# PIC.net
KiCad netlist of a schematic drawn in Altium Designer
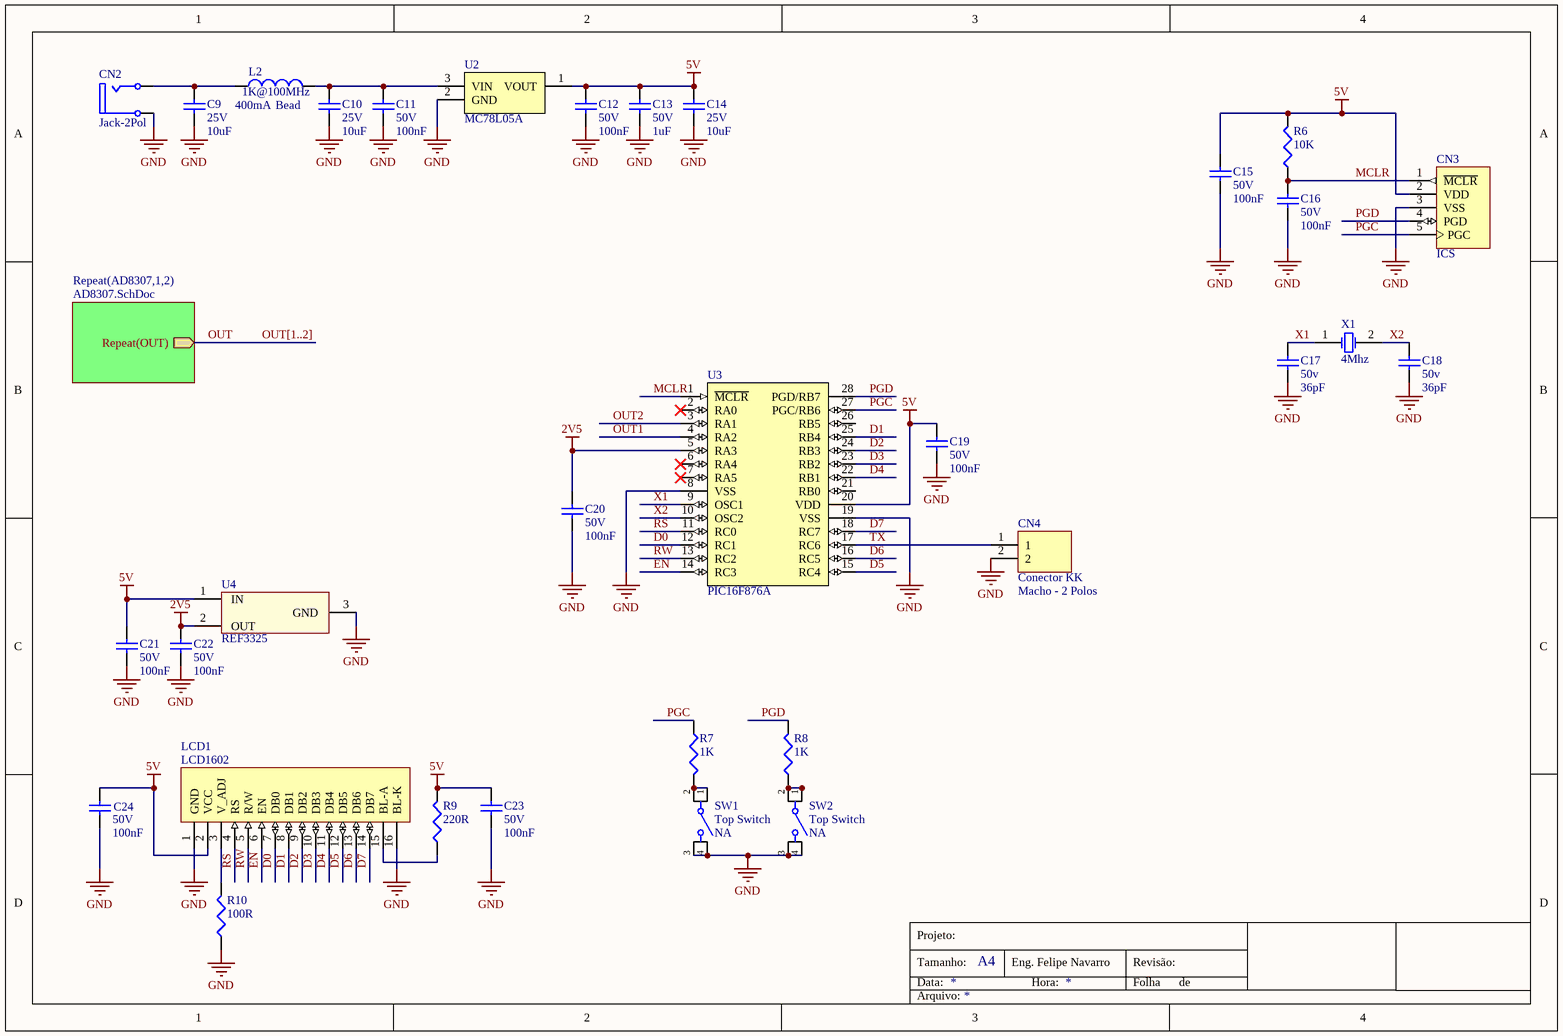
[diagram p0: PIC.SchDoc]

(export (version "E")
  (design (tool "Eeschema 10.0.6"))
  (components
    (comp (ref "C9")
      (value "10uF")
      (footprint "CC0805")
      (description "Capacitor (Semiconductor SIM Model)")
      (fields (field (name "TENSÃO") "25V") (field (name "Comment") "Capacitor Cerâmico"))
      (libsource (lib "NavarroCAP") (part "Cap 10uF 25V 0805 X5R"))
    )
    (comp (ref "C10")
      (value "10uF")
      (footprint "CC0805")
      (description "Capacitor (Semiconductor SIM Model)")
      (fields (field (name "TENSÃO") "25V") (field (name "Comment") "Capacitor Cerâmico"))
      (libsource (lib "NavarroCAP") (part "Cap 10uF 25V 0805 X5R"))
    )
    (comp (ref "C11")
      (value "100nF")
      (footprint "CC0603")
      (description "Capacitor (Semiconductor SIM Model)")
      (fields (field (name "TENSÃO") "50V") (field (name "Comment") "Capacitor Cerâmico"))
      (libsource (lib "NavarroCAP") (part "Cap 100nF 50V 0603 X7R"))
    )
    (comp (ref "C12")
      (value "100nF")
      (footprint "CC0603")
      (description "Capacitor (Semiconductor SIM Model)")
      (fields (field (name "TENSÃO") "50V") (field (name "Comment") "Capacitor Cerâmico"))
      (libsource (lib "NavarroCAP") (part "Cap 100nF 50V 0603 X7R"))
    )
    (comp (ref "C13")
      (value "1uF")
      (footprint "CC0603")
      (description "Capacitor (Semiconductor SIM Model)")
      (fields (field (name "TENSÃO") "50V") (field (name "Comment") "Capacitor Cerâmico"))
      (libsource (lib "NavarroCAP") (part "Cap 1uF 50V 0603 X5R"))
    )
    (comp (ref "C14")
      (value "10uF")
      (footprint "CC0805")
      (description "Capacitor (Semiconductor SIM Model)")
      (fields (field (name "TENSÃO") "25V") (field (name "Comment") "Capacitor Cerâmico"))
      (libsource (lib "NavarroCAP") (part "Cap 10uF 25V 0805 X5R"))
    )
    (comp (ref "C15")
      (value "100nF")
      (footprint "CC0603")
      (description "Capacitor (Semiconductor SIM Model)")
      (fields (field (name "TENSÃO") "50V") (field (name "Comment") "Capacitor Cerâmico"))
      (libsource (lib "NavarroCAP") (part "Cap 100nF 50V 0603 X7R"))
    )
    (comp (ref "C16")
      (value "100nF")
      (footprint "CC0603")
      (description "Capacitor (Semiconductor SIM Model)")
      (fields (field (name "TENSÃO") "50V") (field (name "Comment") "Capacitor Cerâmico"))
      (libsource (lib "NavarroCAP") (part "Cap 100nF 50V 0603 X7R"))
    )
    (comp (ref "C17")
      (value "36pF")
      (footprint "CC0603")
      (description "Capacitor (Semiconductor SIM Model)")
      (fields (field (name "TENSÃO") "50v") (field (name "Comment") "Capacitor Cerâmico"))
      (libsource (lib "NavarroCAP") (part "Cap - $Val $V $Footprint $Classe_1"))
    )
    (comp (ref "C18")
      (value "36pF")
      (footprint "CC0603")
      (description "Capacitor (Semiconductor SIM Model)")
      (fields (field (name "TENSÃO") "50v") (field (name "Comment") "Capacitor Cerâmico"))
      (libsource (lib "NavarroCAP") (part "Cap - $Val $V $Footprint $Classe_1"))
    )
    (comp (ref "C19")
      (value "100nF")
      (footprint "CC0603")
      (description "Capacitor (Semiconductor SIM Model)")
      (fields (field (name "TENSÃO") "50V") (field (name "Comment") "Capacitor Cerâmico"))
      (libsource (lib "NavarroCAP") (part "Cap 100nF 50V 0603 X7R"))
    )
    (comp (ref "C20")
      (value "100nF")
      (footprint "CC0603")
      (description "Capacitor (Semiconductor SIM Model)")
      (fields (field (name "TENSÃO") "50V") (field (name "Comment") "Capacitor Cerâmico"))
      (libsource (lib "NavarroCAP") (part "Cap 100nF 50V 0603 X7R"))
    )
    (comp (ref "C21")
      (value "100nF")
      (footprint "CC0603")
      (description "Capacitor (Semiconductor SIM Model)")
      (fields (field (name "TENSÃO") "50V") (field (name "Comment") "Capacitor Cerâmico"))
      (libsource (lib "NavarroCAP") (part "Cap 100nF 50V 0603 X7R"))
    )
    (comp (ref "C22")
      (value "100nF")
      (footprint "CC0603")
      (description "Capacitor (Semiconductor SIM Model)")
      (fields (field (name "TENSÃO") "50V") (field (name "Comment") "Capacitor Cerâmico"))
      (libsource (lib "NavarroCAP") (part "Cap 100nF 50V 0603 X7R"))
    )
    (comp (ref "C23")
      (value "100nF")
      (footprint "CC0603")
      (description "Capacitor (Semiconductor SIM Model)")
      (fields (field (name "TENSÃO") "50V") (field (name "Comment") "Capacitor Cerâmico"))
      (libsource (lib "NavarroCAP") (part "Cap 100nF 50V 0603 X7R"))
    )
    (comp (ref "C24")
      (value "100nF")
      (footprint "CC0603")
      (description "Capacitor (Semiconductor SIM Model)")
      (fields (field (name "TENSÃO") "50V") (field (name "Comment") "Capacitor Cerâmico"))
      (libsource (lib "NavarroCAP") (part "Cap 100nF 50V 0603 X7R"))
    )
    (comp (ref "CN2")
      (value "Jack-2Pol")
      (footprint "CONN_JACK-FONTE")
      (description "Jack Socket, Thru-Hole, Vertical, 2-Conductor Open Circuit")
      (libsource (lib "NavarroCON") (part "Jack-2Pol"))
    )
    (comp (ref "CN3")
      (value "ICS")
      (footprint "CONN HDR1X5")
      (description "Header, 5-Pin")
      (libsource (lib "NavarroCON") (part "Header 5 ICS"))
    )
    (comp (ref "CN4")
      (value "Conector KK")
      (footprint "CONN HDR2-POL P.100")
      (fields (field (name "ALTIUM_VALUE") "Macho - 2 Polos"))
      (libsource (lib "NavarroCON") (part "KK 2P Macho-V P2.54mm"))
    )
    (comp (ref "L2")
      (value "Bead")
      (footprint "CC0603")
      (fields (field (name "CORRENTE") "400mA") (field (name "ALTIUM_VALUE") "1K@100MHz"))
      (libsource (lib "NavarroIND") (part "Bd 1K@100MHz 0603 400mA"))
    )
    (comp (ref "LCD1")
      (value "LCD1602")
      (footprint "LCD-1602")
      (description "LCD Generico 16 caracteres X 2 linhas")
      (libsource (lib "Navarro") (part "LCD1602"))
    )
    (comp (ref "R6")
      (value "10K")
      (footprint "CC0603")
      (description "Resistor")
      (libsource (lib "NavarroRES") (part "Res 10K 1% 0603 1/10W"))
    )
    (comp (ref "R7")
      (value "1K")
      (footprint "CC0603")
      (description "Resistor")
      (libsource (lib "NavarroRES") (part "Res 1K 1% 0603 1/10W"))
    )
    (comp (ref "R8")
      (value "1K")
      (footprint "CC0603")
      (description "Resistor")
      (libsource (lib "NavarroRES") (part "Res 1K 1% 0603 1/10W"))
    )
    (comp (ref "R9")
      (value "220R")
      (footprint "CC0603")
      (description "Resistor")
      (libsource (lib "NavarroRES") (part "Res 220R 1% 0603 1/10W"))
    )
    (comp (ref "R10")
      (value "100R")
      (footprint "CC0603")
      (description "Resistor")
      (libsource (lib "NavarroRES") (part "Res 220R 1% 0603 1/10W"))
    )
    (comp (ref "SW1")
      (value "Top Switch")
      (footprint "SWITCH-TACTIL_6x6")
      (description "Single-Pole, Single-Throw Switch")
      (fields (field (name "ALTIUM_VALUE") "NA"))
      (libsource (lib "Tecnoclade") (part "SW-SPST Tactil"))
    )
    (comp (ref "SW2")
      (value "Top Switch")
      (footprint "SWITCH-TACTIL_6x6")
      (description "Single-Pole, Single-Throw Switch")
      (fields (field (name "ALTIUM_VALUE") "NA"))
      (libsource (lib "Tecnoclade") (part "SW-SPST Tactil"))
    )
    (comp (ref "U2")
      (value "MC78L05A")
      (footprint "SOT-89-3N")
      (description "Regulador Linear 5V")
      (libsource (lib "Navarro") (part "MC78L05"))
    )
    (comp (ref "U3")
      (value "PIC16F876A")
      (footprint "SOIC-28N")
      (description "Microcontrolador PIC")
      (libsource (lib "Navarro") (part "PIC16F876A"))
    )
    (comp (ref "U4")
      (value "REF3325")
      (footprint "SOT-23-3N")
      (description "IC VREF SERIES 2.5V")
      (libsource (lib "Navarro") (part "REF3325"))
    )
    (comp (ref "X1")
      (value "4Mhz")
      (footprint "HC/49US")
      (description "Crystal Oscillator")
      (libsource (lib "Navarro") (part "XTAL"))
    )
  )
  (nets
    (net (code "1") (name "/D0") (class "Default")
      (node (ref "LCD1") (pin "7") (pinfunction "DB0_7") (pintype "bidirectional"))
      (node (ref "U3") (pin "12") (pinfunction "RC1_12") (pintype "bidirectional"))
    )
    (net (code "2") (name "/D1") (class "Default")
      (node (ref "LCD1") (pin "8") (pinfunction "DB1_8") (pintype "bidirectional"))
      (node (ref "U3") (pin "25") (pinfunction "RB4_25") (pintype "bidirectional"))
    )
    (net (code "3") (name "/D2") (class "Default")
      (node (ref "LCD1") (pin "9") (pinfunction "DB2_9") (pintype "bidirectional"))
      (node (ref "U3") (pin "24") (pinfunction "RB3_24") (pintype "bidirectional"))
    )
    (net (code "4") (name "/D3") (class "Default")
      (node (ref "LCD1") (pin "10") (pinfunction "DB3_10") (pintype "bidirectional"))
      (node (ref "U3") (pin "23") (pinfunction "RB2_23") (pintype "bidirectional"))
    )
    (net (code "5") (name "/D4") (class "Default")
      (node (ref "LCD1") (pin "11") (pinfunction "DB4_11") (pintype "bidirectional"))
      (node (ref "U3") (pin "22") (pinfunction "RB1_22") (pintype "bidirectional"))
    )
    (net (code "6") (name "/D5") (class "Default")
      (node (ref "LCD1") (pin "12") (pinfunction "DB5_12") (pintype "bidirectional"))
      (node (ref "U3") (pin "15") (pinfunction "RC4_15") (pintype "bidirectional"))
    )
    (net (code "7") (name "/D6") (class "Default")
      (node (ref "LCD1") (pin "13") (pinfunction "DB6_13") (pintype "bidirectional"))
      (node (ref "U3") (pin "16") (pinfunction "RC5_16") (pintype "bidirectional"))
    )
    (net (code "8") (name "/D7") (class "Default")
      (node (ref "LCD1") (pin "14") (pinfunction "DB7_14") (pintype "bidirectional"))
      (node (ref "U3") (pin "18") (pinfunction "RC7_18") (pintype "bidirectional"))
    )
    (net (code "9") (name "/EN") (class "Default")
      (node (ref "LCD1") (pin "6") (pinfunction "EN_6") (pintype "input"))
      (node (ref "U3") (pin "14") (pinfunction "RC3_14") (pintype "bidirectional"))
    )
    (net (code "10") (name "/MCLR") (class "Default")
      (node (ref "C16") (pin "2") (pinfunction "2_2") (pintype "passive"))
      (node (ref "CN3") (pin "1") (pinfunction "~{MCLR}_1") (pintype "output"))
      (node (ref "R6") (pin "1") (pinfunction "1_1") (pintype "passive"))
      (node (ref "U3") (pin "1") (pinfunction "MCLR_1") (pintype "input"))
    )
    (net (code "12") (name "/OUT1") (class "Default")
      (node (ref "U3") (pin "4") (pinfunction "RA2_4") (pintype "bidirectional"))
    )
    (net (code "13") (name "/OUT2") (class "Default")
      (node (ref "U3") (pin "3") (pinfunction "RA1_3") (pintype "bidirectional"))
    )
    (net (code "15") (name "/PGC") (class "Default")
      (node (ref "CN3") (pin "5") (pinfunction "PGC_5") (pintype "passive"))
      (node (ref "R7") (pin "1") (pinfunction "1_1") (pintype "passive"))
      (node (ref "U3") (pin "27") (pinfunction "PGC/RB6_27") (pintype "bidirectional"))
    )
    (net (code "16") (name "/PGD") (class "Default")
      (node (ref "CN3") (pin "4") (pinfunction "PGD_4") (pintype "bidirectional"))
      (node (ref "R8") (pin "2") (pinfunction "2_2") (pintype "passive"))
      (node (ref "U3") (pin "28") (pinfunction "PGD/RB7_28") (pintype "power_in"))
    )
    (net (code "17") (name "/RS") (class "Default")
      (node (ref "LCD1") (pin "4") (pinfunction "RS_4") (pintype "input"))
      (node (ref "U3") (pin "11") (pinfunction "RC0_11") (pintype "bidirectional"))
    )
    (net (code "18") (name "/RW") (class "Default")
      (node (ref "LCD1") (pin "5") (pinfunction "R/W_5") (pintype "input"))
      (node (ref "U3") (pin "13") (pinfunction "RC2_13") (pintype "bidirectional"))
    )
    (net (code "19") (name "/TX") (class "Default")
      (node (ref "CN4") (pin "1") (pinfunction "1_1") (pintype "passive"))
      (node (ref "U3") (pin "17") (pinfunction "RC6_17") (pintype "bidirectional"))
    )
    (net (code "20") (name "/X1") (class "Default")
      (node (ref "C17") (pin "2") (pinfunction "2_2") (pintype "passive"))
      (node (ref "U3") (pin "9") (pinfunction "OSC1_9") (pintype "bidirectional"))
      (node (ref "X1") (pin "1") (pinfunction "OSC1_1") (pintype "passive"))
    )
    (net (code "21") (name "/X2") (class "Default")
      (node (ref "C18") (pin "2") (pinfunction "2_2") (pintype "passive"))
      (node (ref "U3") (pin "10") (pinfunction "OSC2_10") (pintype "bidirectional"))
      (node (ref "X1") (pin "2") (pinfunction "OSC2_2") (pintype "passive"))
    )
    (net (code "22") (name "2V5") (class "Default")
      (node (ref "C20") (pin "2") (pinfunction "2_2") (pintype "passive"))
      (node (ref "C22") (pin "2") (pinfunction "2_2") (pintype "passive"))
      (node (ref "U3") (pin "5") (pinfunction "RA3_5") (pintype "bidirectional"))
      (node (ref "U4") (pin "2") (pinfunction "OUT_2") (pintype "power_in"))
    )
    (net (code "23") (name "5V") (class "Default")
      (node (ref "C12") (pin "2") (pinfunction "2_2") (pintype "passive"))
      (node (ref "C13") (pin "2") (pinfunction "2_2") (pintype "passive"))
      (node (ref "C14") (pin "2") (pinfunction "2_2") (pintype "passive"))
      (node (ref "C15") (pin "2") (pinfunction "2_2") (pintype "passive"))
      (node (ref "C19") (pin "2") (pinfunction "2_2") (pintype "passive"))
      (node (ref "C21") (pin "2") (pinfunction "2_2") (pintype "passive"))
      (node (ref "C23") (pin "2") (pinfunction "2_2") (pintype "passive"))
      (node (ref "C24") (pin "2") (pinfunction "2_2") (pintype "passive"))
      (node (ref "CN3") (pin "2") (pinfunction "VDD_2") (pintype "power_in"))
      (node (ref "LCD1") (pin "2") (pinfunction "VCC_2") (pintype "power_in"))
      (node (ref "R6") (pin "2") (pinfunction "2_2") (pintype "passive"))
      (node (ref "R9") (pin "2") (pinfunction "2_2") (pintype "passive"))
      (node (ref "U2") (pin "1") (pinfunction "VOUT_1") (pintype "power_in"))
      (node (ref "U3") (pin "20") (pinfunction "VDD_20") (pintype "power_in"))
      (node (ref "U4") (pin "1") (pinfunction "IN_1") (pintype "power_in"))
    )
    (net (code "24") (name "GND") (class "Default")
      (node (ref "C10") (pin "1") (pinfunction "1_1") (pintype "passive"))
      (node (ref "C11") (pin "1") (pinfunction "1_1") (pintype "passive"))
      (node (ref "C12") (pin "1") (pinfunction "1_1") (pintype "passive"))
      (node (ref "C13") (pin "1") (pinfunction "1_1") (pintype "passive"))
      (node (ref "C14") (pin "1") (pinfunction "1_1") (pintype "passive"))
      (node (ref "C15") (pin "1") (pinfunction "1_1") (pintype "passive"))
      (node (ref "C16") (pin "1") (pinfunction "1_1") (pintype "passive"))
      (node (ref "C17") (pin "1") (pinfunction "1_1") (pintype "passive"))
      (node (ref "C18") (pin "1") (pinfunction "1_1") (pintype "passive"))
      (node (ref "C19") (pin "1") (pinfunction "1_1") (pintype "passive"))
      (node (ref "C20") (pin "1") (pinfunction "1_1") (pintype "passive"))
      (node (ref "C21") (pin "1") (pinfunction "1_1") (pintype "passive"))
      (node (ref "C22") (pin "1") (pinfunction "1_1") (pintype "passive"))
      (node (ref "C23") (pin "1") (pinfunction "1_1") (pintype "passive"))
      (node (ref "C24") (pin "1") (pinfunction "1_1") (pintype "passive"))
      (node (ref "C9") (pin "1") (pinfunction "1_1") (pintype "passive"))
      (node (ref "CN2") (pin "2") (pinfunction "Malha_2") (pintype "power_in"))
      (node (ref "CN3") (pin "3") (pinfunction "VSS_3") (pintype "power_in"))
      (node (ref "CN4") (pin "2") (pinfunction "2_2") (pintype "passive"))
      (node (ref "LCD1") (pin "1") (pinfunction "GND_1") (pintype "power_in"))
      (node (ref "LCD1") (pin "16") (pinfunction "BL-K_16") (pintype "passive"))
      (node (ref "R10") (pin "1") (pinfunction "1_1") (pintype "passive"))
      (node (ref "SW1") (pin "3") (pinfunction "3_3") (pintype "tri_state"))
      (node (ref "SW1") (pin "4") (pinfunction "4_4") (pintype "tri_state"))
      (node (ref "SW2") (pin "3") (pinfunction "3_3") (pintype "tri_state"))
      (node (ref "SW2") (pin "4") (pinfunction "4_4") (pintype "tri_state"))
      (node (ref "U2") (pin "2") (pinfunction "GND_2") (pintype "power_in"))
      (node (ref "U3") (pin "19") (pinfunction "VSS_19") (pintype "power_in"))
      (node (ref "U3") (pin "8") (pinfunction "VSS_8") (pintype "power_in"))
      (node (ref "U4") (pin "3") (pinfunction "GND_3") (pintype "power_in"))
    )
    (net (code "25") (name "Net-(CN2-Centro)") (class "Default")
      (node (ref "C9") (pin "2") (pinfunction "2_2") (pintype "passive"))
      (node (ref "CN2") (pin "1") (pinfunction "Centro_1") (pintype "passive"))
      (node (ref "L2") (pin "1") (pinfunction "1_1") (pintype "passive"))
    )
    (net (code "26") (name "Net-(LCD1-BL-A)") (class "Default")
      (node (ref "LCD1") (pin "15") (pinfunction "BL-A_15") (pintype "passive"))
      (node (ref "R9") (pin "1") (pinfunction "1_1") (pintype "passive"))
    )
    (net (code "27") (name "Net-(LCD1-V_ADJ)") (class "Default")
      (node (ref "LCD1") (pin "3") (pinfunction "V_ADJ_3") (pintype "power_in"))
      (node (ref "R10") (pin "2") (pinfunction "2_2") (pintype "passive"))
    )
    (net (code "28") (name "Net-(R7-Pad2)") (class "Default")
      (node (ref "R7") (pin "2") (pinfunction "2_2") (pintype "passive"))
      (node (ref "SW1") (pin "1") (pinfunction "1_1") (pintype "tri_state"))
      (node (ref "SW1") (pin "2") (pinfunction "2_2") (pintype "tri_state"))
    )
    (net (code "29") (name "Net-(R8-Pad1)") (class "Default")
      (node (ref "R8") (pin "1") (pinfunction "1_1") (pintype "passive"))
      (node (ref "SW2") (pin "1") (pinfunction "1_1") (pintype "tri_state"))
      (node (ref "SW2") (pin "2") (pinfunction "2_2") (pintype "tri_state"))
    )
    (net (code "30") (name "Net-(U2-VIN)") (class "Default")
      (node (ref "C10") (pin "2") (pinfunction "2_2") (pintype "passive"))
      (node (ref "C11") (pin "2") (pinfunction "2_2") (pintype "passive"))
      (node (ref "L2") (pin "2") (pinfunction "2_2") (pintype "passive"))
      (node (ref "U2") (pin "3") (pinfunction "VIN_3") (pintype "power_in"))
    )
    (net (code "31") (name "unconnected-(U3-RA0-Pad2)") (class "Default")
      (node (ref "U3") (pin "2") (pinfunction "RA0_2") (pintype "bidirectional+no_connect"))
    )
    (net (code "32") (name "unconnected-(U3-RA4-Pad6)") (class "Default")
      (node (ref "U3") (pin "6") (pinfunction "RA4_6") (pintype "bidirectional+no_connect"))
    )
    (net (code "33") (name "unconnected-(U3-RA5-Pad7)") (class "Default")
      (node (ref "U3") (pin "7") (pinfunction "RA5_7") (pintype "bidirectional+no_connect"))
    )
    (net (code "34") (name "unconnected-(U3-RB0-Pad21)") (class "Default")
      (node (ref "U3") (pin "21") (pinfunction "RB0_21") (pintype "bidirectional"))
    )
    (net (code "35") (name "unconnected-(U3-RB5-Pad26)") (class "Default")
      (node (ref "U3") (pin "26") (pinfunction "RB5_26") (pintype "bidirectional"))
    )
  )
)
